# LB_p1_Power-v03_rev2.net
KiCad netlist of a schematic drawn in EAGLE
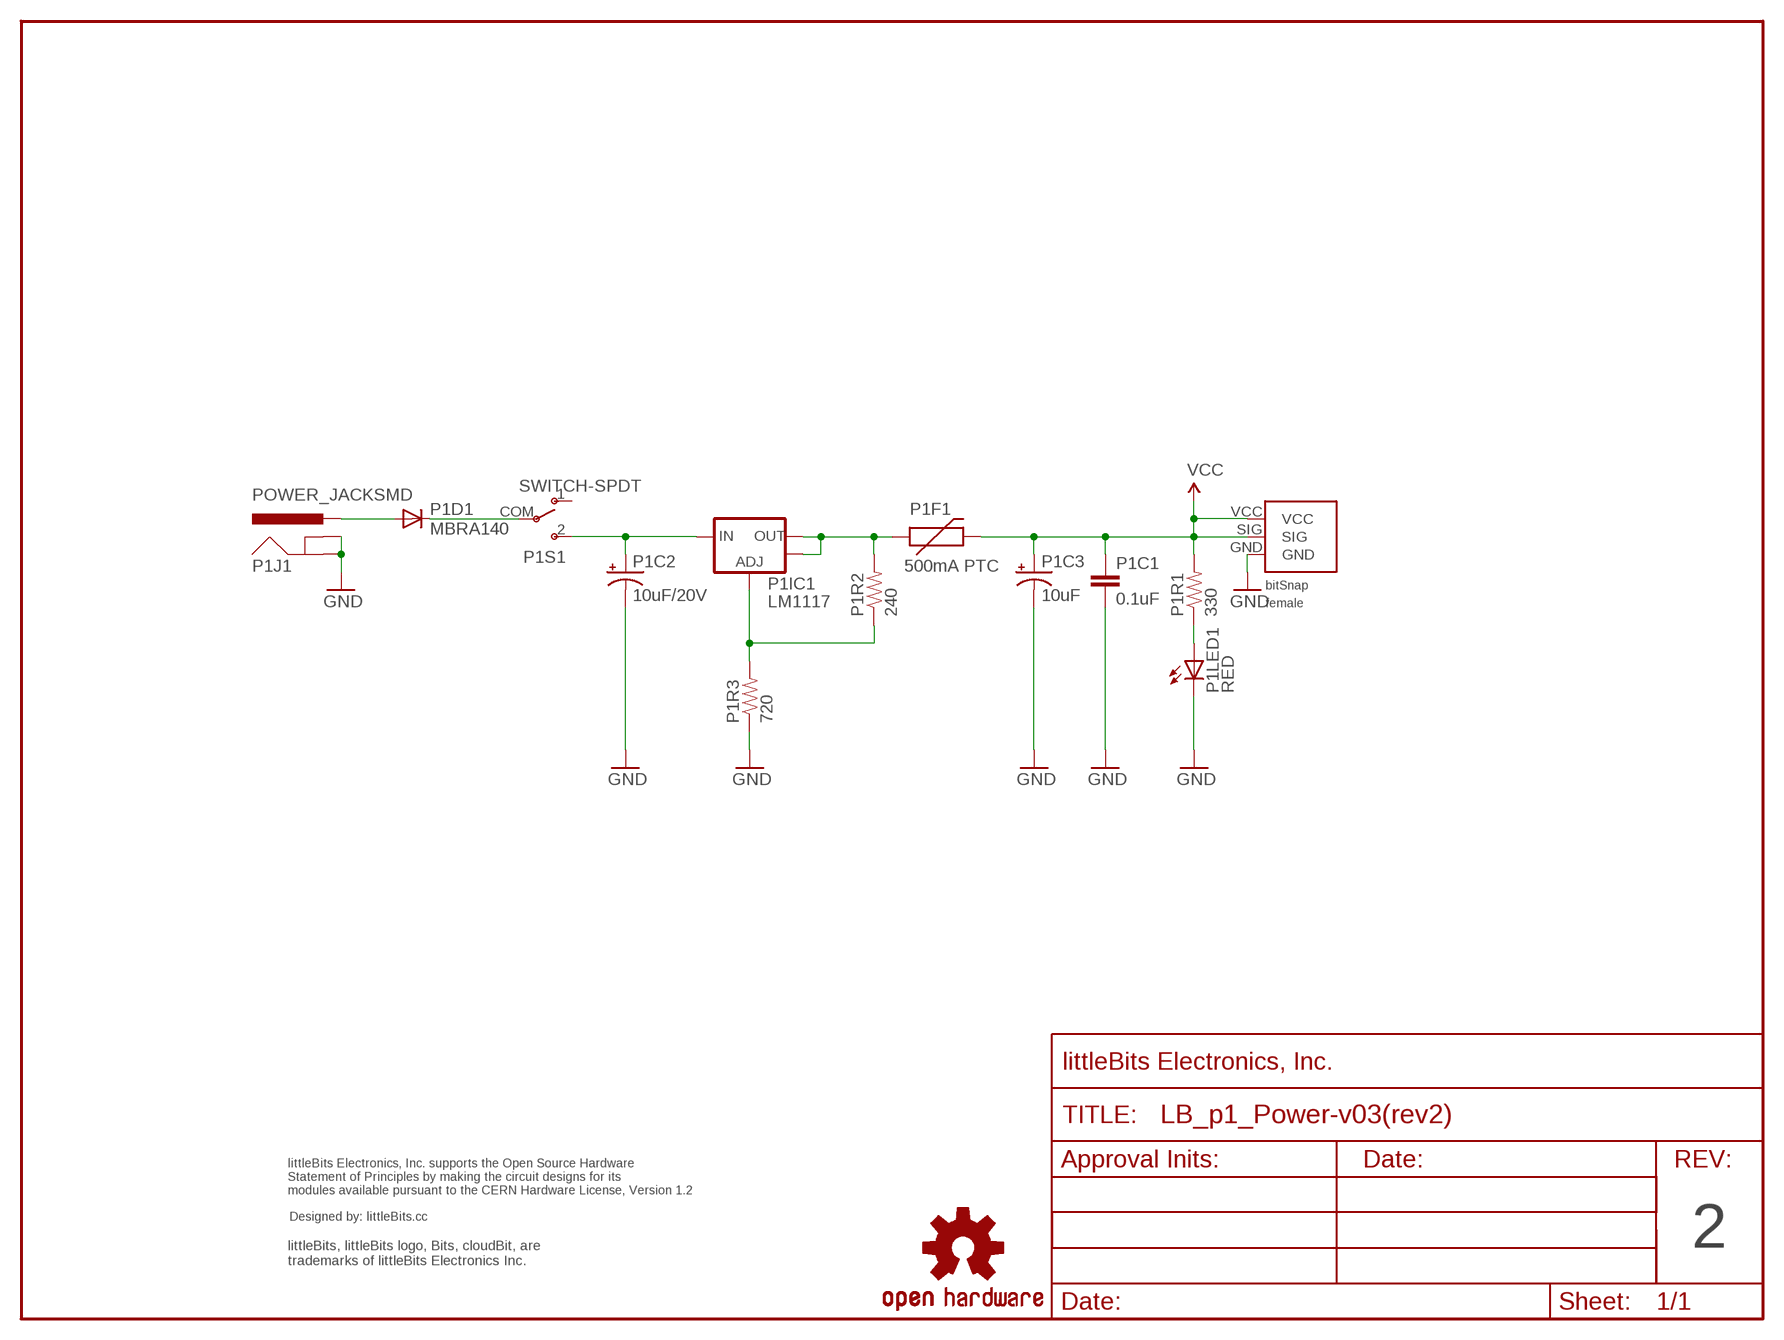
[diagram p0: schematic, sheet 1]

(export (version "E")
  (design (tool "Eeschema 10.0.6"))
  (components
    (comp (ref "P1BSF1")
      (value "BITSNAP_V03_FEMALE")
      (footprint "eagle-import:BITSNAP_V03_FEMALE")
      (libsource (lib "eagle-import") (part "BITSNAP_V03_FEMALE"))
    )
    (comp (ref "P1C1")
      (value "0.1uF")
      (footprint "eagle-import:0603-CAP")
      (libsource (lib "eagle-import") (part "CAP0603-CAP"))
    )
    (comp (ref "P1C2")
      (value "10uF/20V")
      (footprint "eagle-import:EIA3528")
      (libsource (lib "eagle-import") (part "CAP_POL3528"))
    )
    (comp (ref "P1C3")
      (value "10uF")
      (footprint "eagle-import:EIA3216")
      (libsource (lib "eagle-import") (part "CAP_POL1206"))
    )
    (comp (ref "P1D1")
      (value "MBRA140")
      (footprint "eagle-import:SMA-DIODE")
      (libsource (lib "eagle-import") (part "DIODESMA"))
    )
    (comp (ref "P1F1")
      (value "500mA PTC")
      (footprint "eagle-import:PTC-1206")
      (libsource (lib "eagle-import") (part "PTCSMD"))
    )
    (comp (ref "P1IC1")
      (value "LM1117")
      (footprint "eagle-import:SOT223")
      (libsource (lib "eagle-import") (part "V_REG_LM1117SOT223"))
    )
    (comp (ref "P1J1")
      (value "POWER_JACKSMD")
      (footprint "eagle-import:POWER_JACK_SMD")
      (libsource (lib "eagle-import") (part "POWER_JACKSMD"))
    )
    (comp (ref "P1LED1")
      (value "RED")
      (footprint "eagle-import:LED-1206")
      (libsource (lib "eagle-import") (part "LED1206"))
    )
    (comp (ref "P1R1")
      (value "330")
      (footprint "eagle-import:0603-RES")
      (libsource (lib "eagle-import") (part "RESISTOR0603-RES"))
    )
    (comp (ref "P1R2")
      (value "240")
      (footprint "eagle-import:0603-RES")
      (libsource (lib "eagle-import") (part "RESISTOR0603-RES"))
    )
    (comp (ref "P1R3")
      (value "720")
      (footprint "eagle-import:0603-RES")
      (libsource (lib "eagle-import") (part "RESISTOR0603-RES"))
    )
    (comp (ref "P1S1")
      (value "SWITCH-SPDT")
      (footprint "eagle-import:LITTLEBITS_SWITCH-DICGU_SPDT")
      (libsource (lib "eagle-import") (part "SWITCH-DICGU_SPDT"))
    )
    (comp (ref "U$3")
      (value "OSHW-LOGOL")
      (footprint "eagle-import:OSHW-LOGO-L")
      (libsource (lib "eagle-import") (part "OSHW-LOGOL"))
    )
    (comp (ref "U$4")
      (value "LB_CREDITS")
      (footprint "eagle-import:OSHWCREDIT")
      (libsource (lib "eagle-import") (part "LB_CREDITS"))
    )
    (comp (ref "U$5")
      (value "FRAME-LETTER-OHWOHW")
      (footprint "eagle-import:FABDWG01-OHW")
      (libsource (lib "eagle-import") (part "FRAME-LETTER-OHWOHW"))
    )
  )
  (nets
    (net (code "1") (name "GND") (class "Default")
      (node (ref "P1BSF1") (pin "GND") (pinfunction "GND_GND") (pintype "bidirectional"))
      (node (ref "P1C1") (pin "2") (pinfunction "2_2") (pintype "passive"))
      (node (ref "P1C2") (pin "C") (pinfunction "-_C") (pintype "passive"))
      (node (ref "P1C3") (pin "C") (pinfunction "-_C") (pintype "passive"))
      (node (ref "P1J1") (pin "GND") (pinfunction "GNDBREAK_GND") (pintype "bidirectional"))
      (node (ref "P1J1") (pin "P$4") (pinfunction "GND_P$4") (pintype "bidirectional"))
      (node (ref "P1LED1") (pin "C") (pinfunction "C_C") (pintype "passive"))
      (node (ref "P1R3") (pin "1") (pinfunction "1_1") (pintype "passive"))
    )
    (net (code "2") (name "Net-(P1C2-+)") (class "Default")
      (node (ref "P1C2") (pin "A") (pinfunction "+_A") (pintype "passive"))
      (node (ref "P1IC1") (pin "3") (pinfunction "IN_3") (pintype "input"))
      (node (ref "P1S1") (pin "2") (pinfunction "S_2") (pintype "passive"))
    )
    (net (code "3") (name "Net-(P1F1-Pad1)") (class "Default")
      (node (ref "P1F1") (pin "1") (pinfunction "1_1") (pintype "bidirectional"))
      (node (ref "P1IC1") (pin "2") (pinfunction "OUT_2") (pintype "output"))
      (node (ref "P1IC1") (pin "4") (pinfunction "OUT_4") (pintype "output"))
      (node (ref "P1R2") (pin "2") (pinfunction "2_2") (pintype "passive"))
    )
    (net (code "4") (name "Net-(P1IC1-ADJ)") (class "Default")
      (node (ref "P1IC1") (pin "1") (pinfunction "ADJ_1") (pintype "input"))
      (node (ref "P1R2") (pin "1") (pinfunction "1_1") (pintype "passive"))
      (node (ref "P1R3") (pin "2") (pinfunction "2_2") (pintype "passive"))
    )
    (net (code "5") (name "Net-(P1J1-PWR)") (class "Default")
      (node (ref "P1D1") (pin "A") (pinfunction "A_A") (pintype "passive"))
      (node (ref "P1J1") (pin "VIN0") (pinfunction "PWR_VIN0") (pintype "bidirectional"))
    )
    (net (code "6") (name "Net-(P1LED1-PadA)") (class "Default")
      (node (ref "P1LED1") (pin "A") (pinfunction "A_A") (pintype "passive"))
      (node (ref "P1R1") (pin "1") (pinfunction "1_1") (pintype "passive"))
    )
    (net (code "7") (name "Net-(P1S1-P)") (class "Default")
      (node (ref "P1D1") (pin "C") (pinfunction "C_C") (pintype "passive"))
      (node (ref "P1S1") (pin "COM") (pinfunction "P_COM") (pintype "passive"))
    )
    (net (code "8") (name "VCC") (class "Default")
      (node (ref "P1BSF1") (pin "SIG") (pinfunction "SIG_SIG") (pintype "bidirectional"))
      (node (ref "P1BSF1") (pin "VCC") (pinfunction "VCC_VCC") (pintype "bidirectional"))
      (node (ref "P1C1") (pin "1") (pinfunction "1_1") (pintype "passive"))
      (node (ref "P1C3") (pin "A") (pinfunction "+_A") (pintype "passive"))
      (node (ref "P1F1") (pin "2") (pinfunction "2_2") (pintype "bidirectional"))
      (node (ref "P1R1") (pin "2") (pinfunction "2_2") (pintype "passive"))
    )
    (net (code "9") (name "unconnected-(P1S1-O-Pad1)") (class "Default")
      (node (ref "P1S1") (pin "1") (pinfunction "O_1") (pintype "passive"))
    )
  )
)
